# CAN_IF.net
KiCad netlist of a schematic drawn in Altium Designer
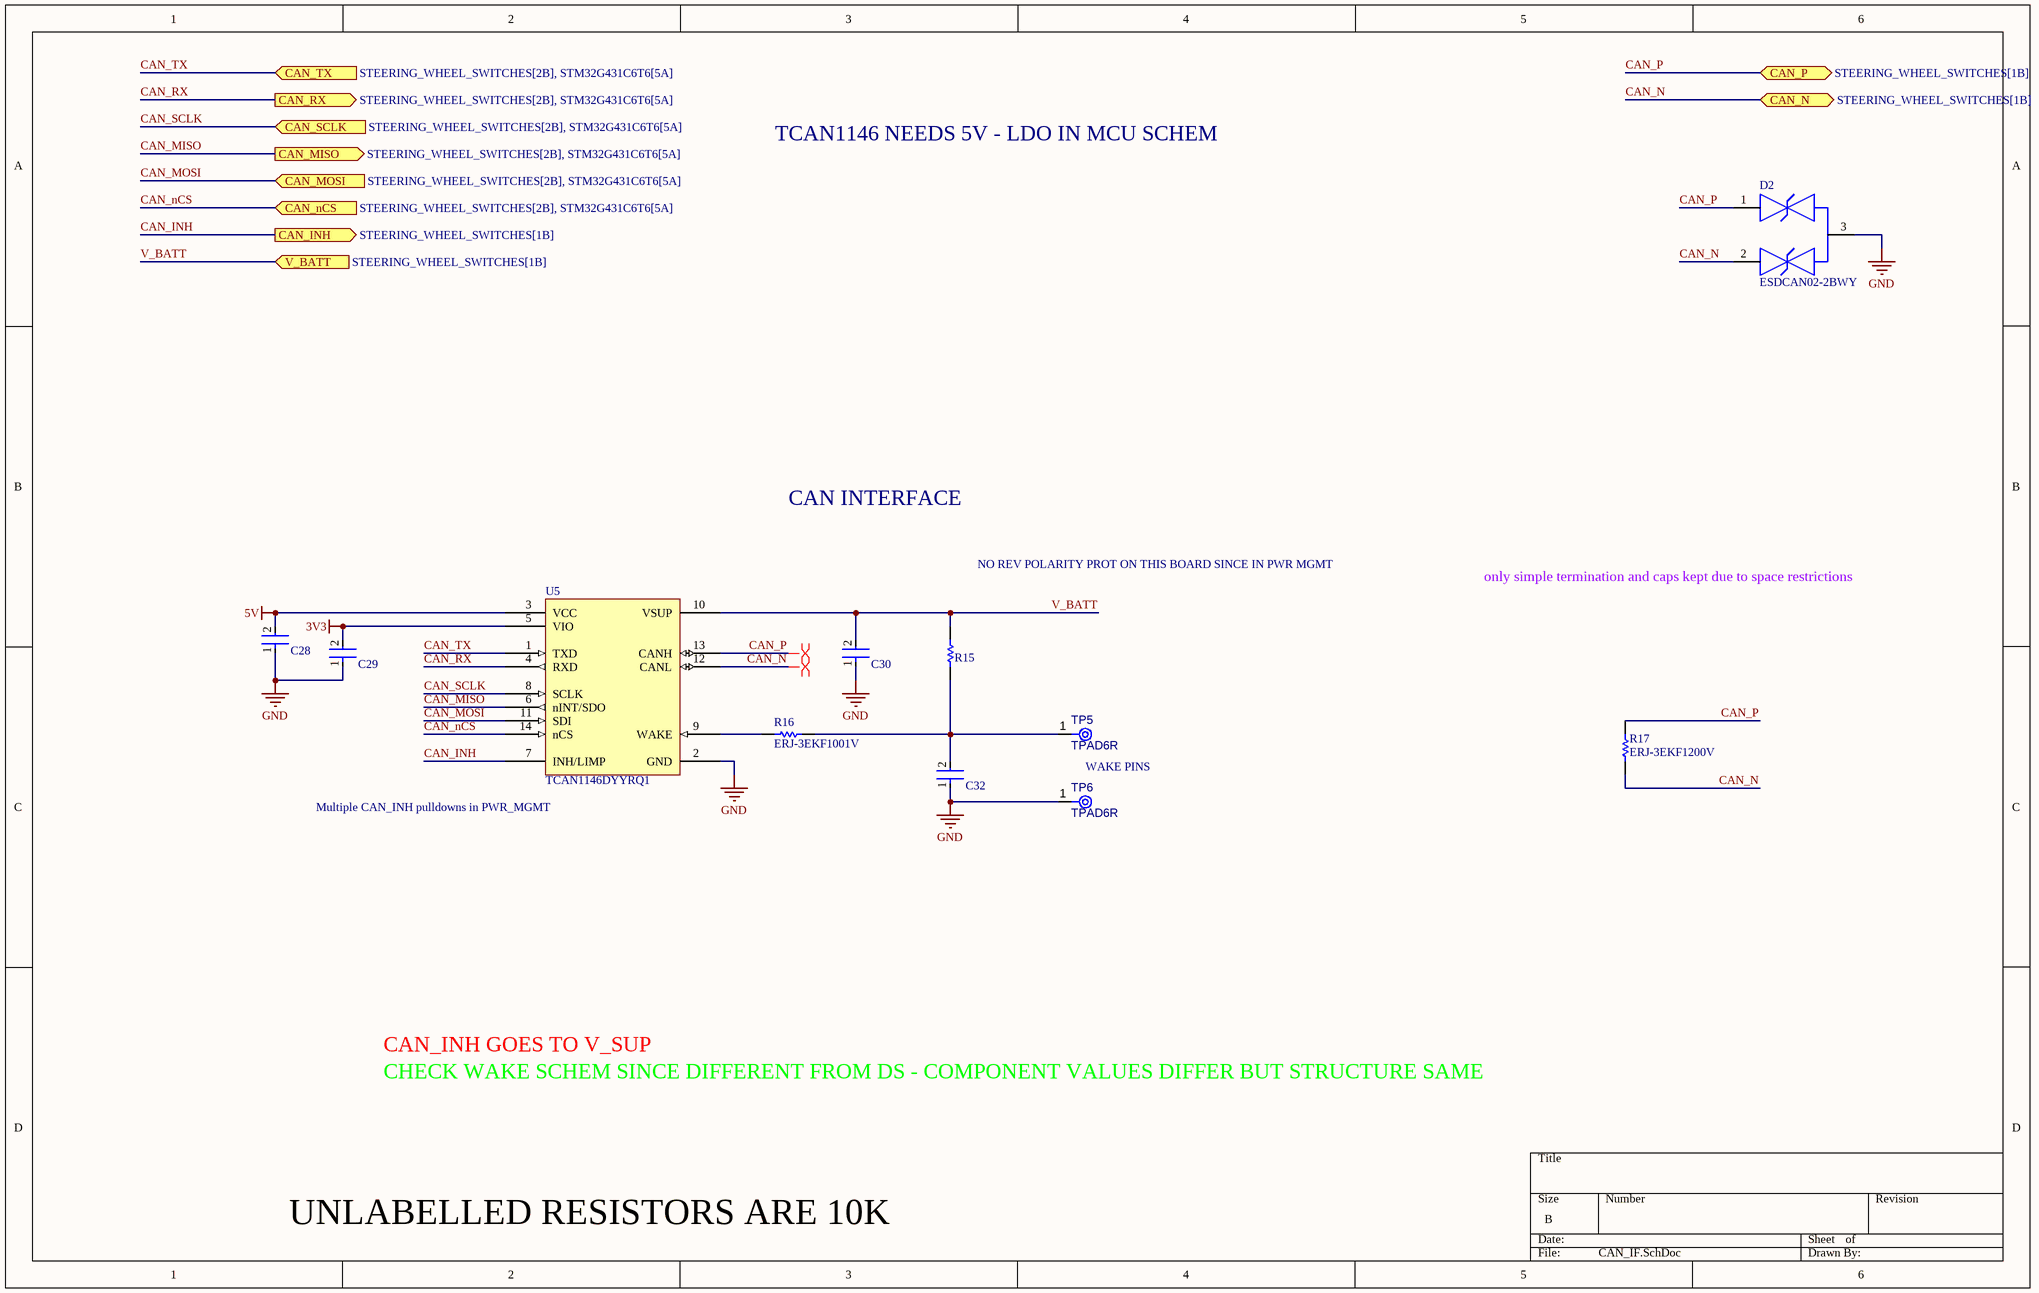
[diagram p0: CAN_IF.SchDoc]

(export (version "E")
  (design (tool "Eeschema 10.0.6"))
  (components
    (comp (ref "C28")
      (value "C0402C104K8PACTU")
      (footprint "FP-C0402-BB-MFG")
      (description "CAP CER 0.1UF 10V X5R 0402")
      (fields (field (name "MANUFACTURER") "Kemet") (field (name "TOLERANCE") "0.1"))
      (libsource (lib "Altium Content Vault") (part "b4654b650e69147ec39a6b967a45e02"))
    )
    (comp (ref "C29")
      (value "C0402C104K8PACTU")
      (footprint "FP-C0402-BB-MFG")
      (description "CAP CER 0.1UF 10V X5R 0402")
      (fields (field (name "MANUFACTURER") "Kemet") (field (name "TOLERANCE") "0.1"))
      (libsource (lib "Altium Content Vault") (part "b4654b650e69147ec39a6b967a45e02"))
    )
    (comp (ref "C30")
      (value "C0402C104K8PACTU")
      (footprint "FP-C0402-BB-MFG")
      (description "CAP CER 0.1UF 10V X5R 0402")
      (fields (field (name "MANUFACTURER") "Kemet") (field (name "TOLERANCE") "0.1"))
      (libsource (lib "Altium Content Vault") (part "b4654b650e69147ec39a6b967a45e02"))
    )
    (comp (ref "C32")
      (value "C0402C104K8PACTU")
      (footprint "FP-C0402-BB-MFG")
      (description "CAP CER 0.1UF 10V X5R 0402")
      (fields (field (name "MANUFACTURER") "Kemet") (field (name "TOLERANCE") "0.1"))
      (libsource (lib "Altium Content Vault") (part "b4654b650e69147ec39a6b967a45e02"))
    )
    (comp (ref "D2")
      (value "ESDCAN02-2BWY")
      (footprint "FP-SOT323-3L-MFG")
      (description "TVS DIODE 26.5V 44V SOT323-3")
      (fields
        (field (name "MANUFACTURER") "STMicroelectronics")
        (field (name "OCTOPART") "https://octopart.com/esdcan02-2bwy-stmicroelectronics-58631133")
      )
      (libsource (lib "Altium Content Vault") (part "0b9019fb5e52ed66df21ec1535be59d"))
    )
    (comp (ref "R15")
      (value "ERJ3EKF1002V")
      (footprint "RESC1609X55X30LL15T15")
      (description "Chip Resistor, 10 KOhm, +/- 1%, 0.1 W, -55 to 155 degC, 0603 (1608 Metric), RoHS, Tape and Reel")
      (fields (field (name "TOLERANCE") "1%") (field (name "MANUFACTURER") "Panasonic"))
      (libsource (lib "Altium Content Vault") (part "RES-2"))
    )
    (comp (ref "R16")
      (value "ERJ-3EKF1001V")
      (footprint "RESC1608X55X30LL15T15")
      (fields (field (name "MANUFACTURER") "Panasonic"))
      (libsource (lib "Altium Content Vault") (part "RES"))
    )
    (comp (ref "R17")
      (value "ERJ-3EKF1200V")
      (footprint "RESC1609X55X30ML15T15")
      (description "Chip Resistor, 120 Ohm, +/- 1%, 0.1 W, -55 to 155 degC, 0603 (1608 Metric), RoHS, Tape and Reel")
      (fields (field (name "TOLERANCE") "1%") (field (name "MANUFACTURER") "Panasonic"))
      (libsource (lib "Altium Content Vault") (part "RES-2"))
    )
    (comp (ref "TP5")
      (value "TPAD6R")
      (footprint "TP06R")
      (description "0.6mm round")
      (libsource (lib "uORocketry Hardware") (part "CMP-001-0001-4"))
    )
    (comp (ref "TP6")
      (value "TPAD6R")
      (footprint "TP06R")
      (description "0.6mm round")
      (libsource (lib "uORocketry Hardware") (part "CMP-001-0001-4"))
    )
    (comp (ref "U5")
      (value "TCAN1146DYYRQ1")
      (footprint "TCAN1146DYYRQ1-Footprint-1")
      (libsource (lib "uORocketry Hardware") (part "TCAN1146DYYRQ1"))
    )
  )
  (nets
    (net (code "1") (name "/CAN_INH") (class "Default")
      (node (ref "U5") (pin "7") (pinfunction "INH/LIMP_7") (pintype "passive"))
    )
    (net (code "2") (name "/CAN_MISO") (class "Default")
      (node (ref "U5") (pin "6") (pinfunction "nINT/SDO_6") (pintype "output"))
    )
    (net (code "3") (name "/CAN_MOSI") (class "Default")
      (node (ref "U5") (pin "11") (pinfunction "SDI_11") (pintype "input"))
    )
    (net (code "4") (name "/CAN_N") (class "Default")
      (node (ref "D2") (pin "2") (pinfunction "2_2") (pintype "passive"))
      (node (ref "R17") (pin "2") (pinfunction "2_2") (pintype "passive"))
      (node (ref "U5") (pin "12") (pinfunction "CANL_12") (pintype "bidirectional"))
    )
    (net (code "5") (name "/CAN_P") (class "Default")
      (node (ref "D2") (pin "1") (pinfunction "1_1") (pintype "passive"))
      (node (ref "R17") (pin "1") (pinfunction "1_1") (pintype "passive"))
      (node (ref "U5") (pin "13") (pinfunction "CANH_13") (pintype "bidirectional"))
    )
    (net (code "6") (name "/CAN_RX") (class "Default")
      (node (ref "U5") (pin "4") (pinfunction "RXD_4") (pintype "output"))
    )
    (net (code "7") (name "/CAN_SCLK") (class "Default")
      (node (ref "U5") (pin "8") (pinfunction "SCLK_8") (pintype "input"))
    )
    (net (code "8") (name "/CAN_TX") (class "Default")
      (node (ref "U5") (pin "1") (pinfunction "TXD_1") (pintype "input"))
    )
    (net (code "9") (name "/CAN_nCS") (class "Default")
      (node (ref "U5") (pin "14") (pinfunction "nCS_14") (pintype "input"))
    )
    (net (code "10") (name "/V_BATT") (class "Default")
      (node (ref "C30") (pin "2") (pinfunction "2_2") (pintype "passive"))
      (node (ref "R15") (pin "1") (pinfunction "1_1") (pintype "passive"))
      (node (ref "U5") (pin "10") (pinfunction "VSUP_10") (pintype "power_in"))
    )
    (net (code "11") (name "3V3") (class "Default")
      (node (ref "C29") (pin "2") (pinfunction "2_2") (pintype "passive"))
      (node (ref "U5") (pin "5") (pinfunction "VIO_5") (pintype "power_in"))
    )
    (net (code "12") (name "5V") (class "Default")
      (node (ref "C28") (pin "2") (pinfunction "2_2") (pintype "passive"))
      (node (ref "U5") (pin "3") (pinfunction "VCC_3") (pintype "power_in"))
    )
    (net (code "13") (name "GND") (class "Default")
      (node (ref "C28") (pin "1") (pinfunction "1_1") (pintype "passive"))
      (node (ref "C29") (pin "1") (pinfunction "1_1") (pintype "passive"))
      (node (ref "C30") (pin "1") (pinfunction "1_1") (pintype "passive"))
      (node (ref "C32") (pin "1") (pinfunction "1_1") (pintype "passive"))
      (node (ref "D2") (pin "3") (pinfunction "3_3") (pintype "passive"))
      (node (ref "TP6") (pin "1") (pinfunction "TP_1") (pintype "passive"))
      (node (ref "U5") (pin "2") (pinfunction "GND_2") (pintype "power_in"))
    )
    (net (code "14") (name "Net-(TP5-TP)") (class "Default")
      (node (ref "C32") (pin "2") (pinfunction "2_2") (pintype "passive"))
      (node (ref "R15") (pin "2") (pinfunction "2_2") (pintype "passive"))
      (node (ref "R16") (pin "2") (pinfunction "2_2") (pintype "passive"))
      (node (ref "TP5") (pin "1") (pinfunction "TP_1") (pintype "passive"))
    )
    (net (code "15") (name "Net-(U5-WAKE)") (class "Default")
      (node (ref "R16") (pin "1") (pinfunction "1_1") (pintype "passive"))
      (node (ref "U5") (pin "9") (pinfunction "WAKE_9") (pintype "input"))
    )
  )
)
